# HIGH_CURR_MOS.net
KiCad netlist of a schematic drawn in Altium Designer
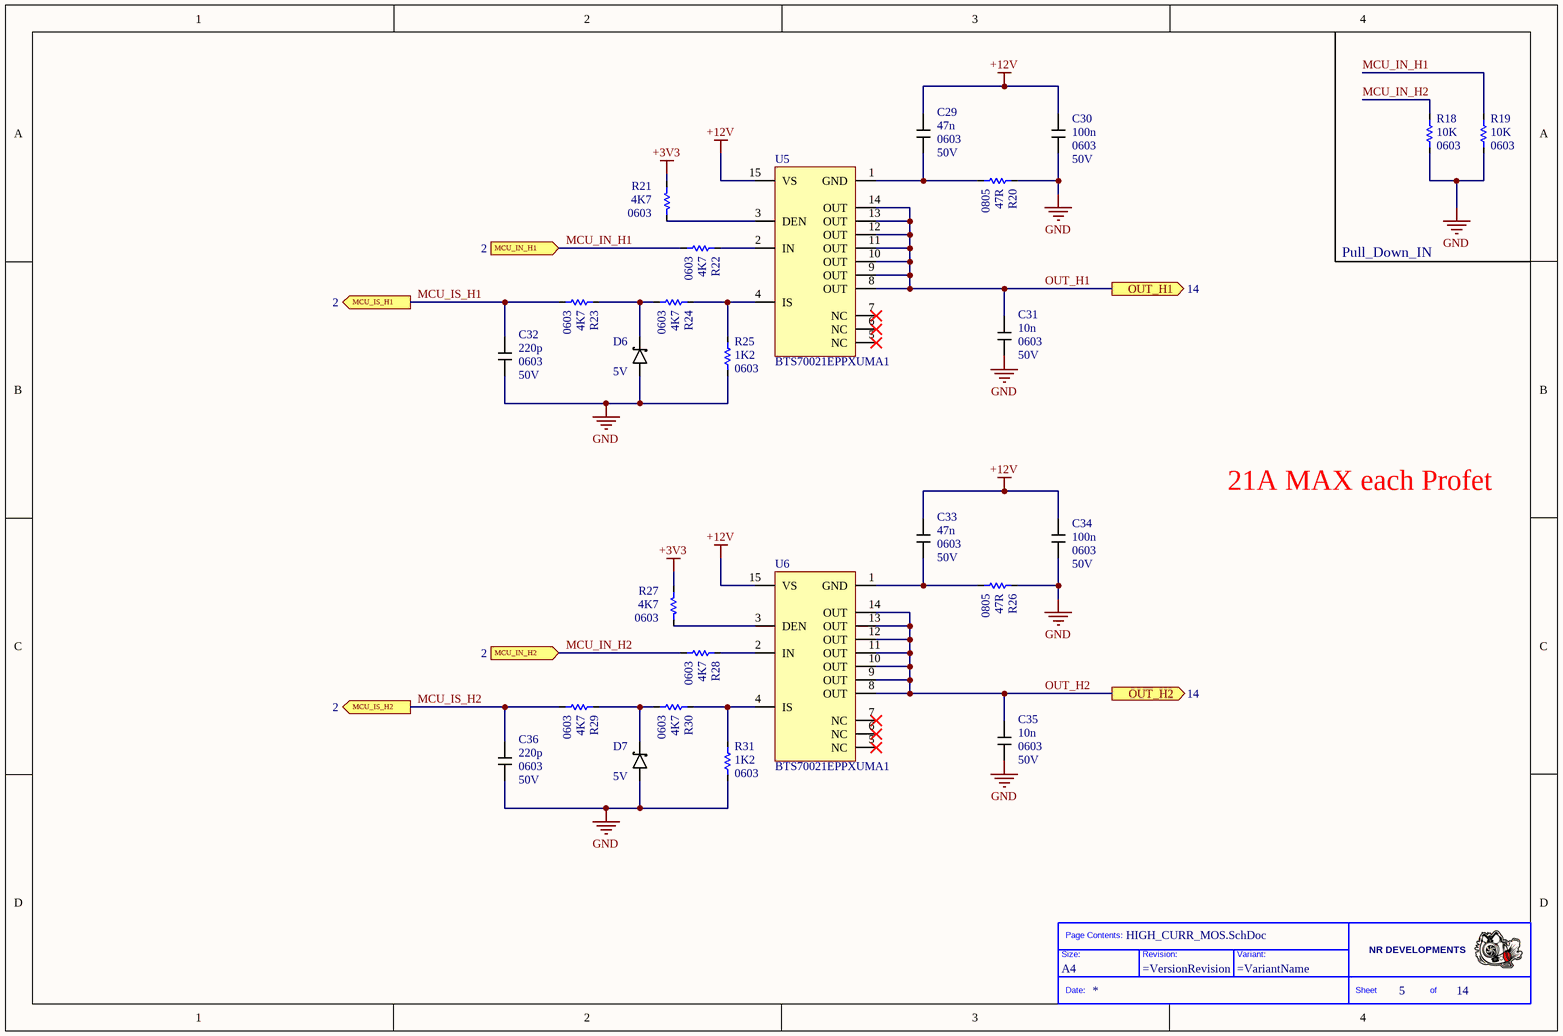
[diagram p0: HIGH_CURR_MOS.SchDoc]

(export (version "E")
  (design (tool "Eeschema 10.0.6"))
  (components
    (comp (ref "C29")
      (value "47n")
      (footprint "CAPC1608X09M")
      (fields
        (field (name "MANUFACTURER") "KEMET")
        (field (name "PARTNUMBER") "C0603C473M5RACTU")
        (field (name "CASE") "0603")
        (field (name "VOLTAGE") "50V")
        (field (name "Comment") "CAP")
      )
      (libsource (lib "My_LIB") (part "CAP"))
    )
    (comp (ref "C30")
      (value "100n")
      (footprint "CAPC1608X09M")
      (fields
        (field (name "CASE") "0603")
        (field (name "VOLTAGE") "50V")
        (field (name "MANUFACTURER") "KEMET")
        (field (name "PARTNUMBER") "C0603C104K5RACTU")
        (field (name "Comment") "CAP")
      )
      (libsource (lib "My_LIB") (part "CAP"))
    )
    (comp (ref "C31")
      (value "10n")
      (footprint "CAPC1608X09M")
      (fields
        (field (name "MANUFACTURER") "KEMET")
        (field (name "PARTNUMBER") "C0603C103M5RACTM")
        (field (name "CASE") "0603")
        (field (name "VOLTAGE") "50V")
        (field (name "Comment") "CAP")
      )
      (libsource (lib "My_LIB") (part "CAP"))
    )
    (comp (ref "C32")
      (value "220p")
      (footprint "CAPC1608X09M")
      (fields
        (field (name "MANUFACTURER") "KEMET")
        (field (name "PARTNUMBER") "C0603C221J5RACTU")
        (field (name "CASE") "0603")
        (field (name "VOLTAGE") "50V")
        (field (name "Comment") "CAP")
      )
      (libsource (lib "My_LIB") (part "CAP"))
    )
    (comp (ref "C33")
      (value "47n")
      (footprint "CAPC1608X09M")
      (fields
        (field (name "MANUFACTURER") "KEMET")
        (field (name "PARTNUMBER") "C0603C473M5RACTU")
        (field (name "CASE") "0603")
        (field (name "VOLTAGE") "50V")
        (field (name "Comment") "CAP")
      )
      (libsource (lib "My_LIB") (part "CAP"))
    )
    (comp (ref "C34")
      (value "100n")
      (footprint "CAPC1608X09M")
      (fields
        (field (name "CASE") "0603")
        (field (name "VOLTAGE") "50V")
        (field (name "MANUFACTURER") "KEMET")
        (field (name "PARTNUMBER") "C0603C104K5RACTU")
        (field (name "Comment") "CAP")
      )
      (libsource (lib "My_LIB") (part "CAP"))
    )
    (comp (ref "C35")
      (value "10n")
      (footprint "CAPC1608X09M")
      (fields
        (field (name "MANUFACTURER") "KEMET")
        (field (name "PARTNUMBER") "C0603C103M5RACTM")
        (field (name "CASE") "0603")
        (field (name "VOLTAGE") "50V")
        (field (name "Comment") "CAP")
      )
      (libsource (lib "My_LIB") (part "CAP"))
    )
    (comp (ref "C36")
      (value "220p")
      (footprint "CAPC1608X09M")
      (fields
        (field (name "MANUFACTURER") "KEMET")
        (field (name "PARTNUMBER") "C0603C221J5RACTU")
        (field (name "CASE") "0603")
        (field (name "VOLTAGE") "50V")
        (field (name "Comment") "CAP")
      )
      (libsource (lib "My_LIB") (part "CAP"))
    )
    (comp (ref "D6")
      (value "5V")
      (footprint "SOT65P210X100-3N - AC")
      (fields
        (field (name "MANUFACTURER") "NEXPERIA")
        (field (name "PARTNUMBER") "BZX84W-C4V7-QX")
        (field (name "Comment") "Diode_Schottky")
      )
      (libsource (lib "My_LIB") (part "Diode_Schottky"))
    )
    (comp (ref "D7")
      (value "5V")
      (footprint "SOT65P210X100-3N - AC")
      (fields
        (field (name "MANUFACTURER") "Nexperia")
        (field (name "PARTNUMBER") "BZX84W-C4V7-QX")
        (field (name "Comment") "Diode_Schottky")
      )
      (libsource (lib "My_LIB") (part "Diode_Schottky"))
    )
    (comp (ref "R18")
      (value "10K")
      (footprint "RESC1608X06M")
      (fields
        (field (name "CASE") "0603")
        (field (name "MANUFACTURER") "YAGEO")
        (field (name "PARTNUMBER") "AC0603FR-0710KL")
        (field (name "Comment") "Res")
      )
      (libsource (lib "My_LIB") (part "Resistor"))
    )
    (comp (ref "R19")
      (value "10K")
      (footprint "RESC1608X06M")
      (fields
        (field (name "CASE") "0603")
        (field (name "MANUFACTURER") "YAGEO")
        (field (name "PARTNUMBER") "AC0603FR-0710KL")
        (field (name "Comment") "Res")
      )
      (libsource (lib "My_LIB") (part "Resistor"))
    )
    (comp (ref "R20")
      (value "47R")
      (footprint "RESC2012X06N")
      (fields
        (field (name "MANUFACTURER") "Vishay")
        (field (name "CASE") "0805")
        (field (name "PARTNUMBER") "CRCW080547R0FKEA")
        (field (name "Comment") "Res")
      )
      (libsource (lib "My_LIB") (part "Resistor"))
    )
    (comp (ref "R21")
      (value "4K7")
      (footprint "RESC1608X06M")
      (fields
        (field (name "CASE") "0603")
        (field (name "MANUFACTURER") "YAGEO")
        (field (name "PARTNUMBER") "RC0603FR-074K7L")
        (field (name "Comment") "Res")
      )
      (libsource (lib "My_LIB") (part "Resistor"))
    )
    (comp (ref "R22")
      (value "4K7")
      (footprint "RESC1608X06M")
      (fields
        (field (name "MANUFACTURER") "YAGEO")
        (field (name "CASE") "0603")
        (field (name "PARTNUMBER") "RC0603FR-074K7L")
        (field (name "Comment") "Res")
      )
      (libsource (lib "My_LIB") (part "Resistor"))
    )
    (comp (ref "R23")
      (value "4K7")
      (footprint "RESC1608X06M")
      (fields
        (field (name "MANUFACTURER") "YAGEO")
        (field (name "CASE") "0603")
        (field (name "PARTNUMBER") "RC0603FR-074K7L")
        (field (name "Comment") "Res")
      )
      (libsource (lib "My_LIB") (part "Resistor"))
    )
    (comp (ref "R24")
      (value "4K7")
      (footprint "RESC1608X06M")
      (fields
        (field (name "MANUFACTURER") "YAGEO")
        (field (name "CASE") "0603")
        (field (name "PARTNUMBER") "RC0603FR-074K7L")
        (field (name "Comment") "Res")
      )
      (libsource (lib "My_LIB") (part "Resistor"))
    )
    (comp (ref "R25")
      (value "1K2")
      (footprint "RESC1608X06M")
      (fields
        (field (name "MANUFACTURER") "Vishay")
        (field (name "CASE") "0603")
        (field (name "PARTNUMBER") "CRCW06031K20FKEA")
        (field (name "Comment") "Res")
      )
      (libsource (lib "My_LIB") (part "Resistor"))
    )
    (comp (ref "R26")
      (value "47R")
      (footprint "RESC2012X06N")
      (fields
        (field (name "MANUFACTURER") "Vishay")
        (field (name "CASE") "0805")
        (field (name "PARTNUMBER") "CRCW080547R0FKEA")
        (field (name "Comment") "Res")
      )
      (libsource (lib "My_LIB") (part "Resistor"))
    )
    (comp (ref "R27")
      (value "4K7")
      (footprint "RESC1608X06M")
      (fields
        (field (name "CASE") "0603")
        (field (name "MANUFACTURER") "YAGEO")
        (field (name "PARTNUMBER") "RC0603FR-074K7L")
        (field (name "Comment") "Res")
      )
      (libsource (lib "My_LIB") (part "Resistor"))
    )
    (comp (ref "R28")
      (value "4K7")
      (footprint "RESC1608X06M")
      (fields
        (field (name "MANUFACTURER") "YAGEO")
        (field (name "CASE") "0603")
        (field (name "PARTNUMBER") "RC0603FR-074K7L")
        (field (name "Comment") "Res")
      )
      (libsource (lib "My_LIB") (part "Resistor"))
    )
    (comp (ref "R29")
      (value "4K7")
      (footprint "RESC1608X06M")
      (fields
        (field (name "MANUFACTURER") "YAGEO")
        (field (name "CASE") "0603")
        (field (name "PARTNUMBER") "RC0603FR-074K7L")
        (field (name "Comment") "Res")
      )
      (libsource (lib "My_LIB") (part "Resistor"))
    )
    (comp (ref "R30")
      (value "4K7")
      (footprint "RESC1608X06M")
      (fields
        (field (name "MANUFACTURER") "YAGEO")
        (field (name "CASE") "0603")
        (field (name "PARTNUMBER") "RC0603FR-074K7L")
        (field (name "Comment") "Res")
      )
      (libsource (lib "My_LIB") (part "Resistor"))
    )
    (comp (ref "R31")
      (value "1K2")
      (footprint "RESC1608X06M")
      (fields
        (field (name "MANUFACTURER") "Vishay")
        (field (name "CASE") "0603")
        (field (name "PARTNUMBER") "CRCW06031K20FKEA")
        (field (name "Comment") "Res")
      )
      (libsource (lib "My_LIB") (part "Resistor"))
    )
    (comp (ref "U5")
      (value "BTS70021EPPXUMA1")
      (footprint "SOP65P600X115-15")
      (description "Smart High-Side Power Switch 21A")
      (fields (field (name "MANUFACTURER") "Infineon Technologies") (field (name "Comment") "BTS7002-1EPP"))
      (libsource (lib "My_LIB") (part "BTS7002-1EPP"))
    )
    (comp (ref "U6")
      (value "BTS70021EPPXUMA1")
      (footprint "SOP65P600X115-15")
      (description "Smart High-Side Power Switch 21A")
      (fields (field (name "MANUFACTURER") "Infineon Technologies") (field (name "Comment") "BTS7002-1EPP"))
      (libsource (lib "My_LIB") (part "BTS7002-1EPP"))
    )
  )
  (nets
    (net (code "1") (name "+3V3") (class "Default")
      (node (ref "R21") (pin "2") (pinfunction "2_2") (pintype "passive"))
      (node (ref "R27") (pin "2") (pinfunction "2_2") (pintype "passive"))
    )
    (net (code "2") (name "+12V") (class "Default")
      (node (ref "C29") (pin "1") (pinfunction "1_1") (pintype "passive"))
      (node (ref "C30") (pin "1") (pinfunction "1_1") (pintype "passive"))
      (node (ref "C33") (pin "1") (pinfunction "1_1") (pintype "passive"))
      (node (ref "C34") (pin "1") (pinfunction "1_1") (pintype "passive"))
      (node (ref "U5") (pin "15") (pinfunction "VS_15") (pintype "power_in"))
      (node (ref "U6") (pin "15") (pinfunction "VS_15") (pintype "power_in"))
    )
    (net (code "3") (name "/MCU_IN_H1") (class "Default")
      (node (ref "R19") (pin "2") (pinfunction "2_2") (pintype "passive"))
      (node (ref "R22") (pin "1") (pinfunction "1_1") (pintype "passive"))
    )
    (net (code "4") (name "/MCU_IN_H2") (class "Default")
      (node (ref "R18") (pin "2") (pinfunction "2_2") (pintype "passive"))
      (node (ref "R28") (pin "1") (pinfunction "1_1") (pintype "passive"))
    )
    (net (code "5") (name "/MCU_IS_H1") (class "Default")
      (node (ref "C32") (pin "1") (pinfunction "1_1") (pintype "passive"))
      (node (ref "R23") (pin "1") (pinfunction "1_1") (pintype "passive"))
    )
    (net (code "6") (name "/MCU_IS_H2") (class "Default")
      (node (ref "C36") (pin "1") (pinfunction "1_1") (pintype "passive"))
      (node (ref "R29") (pin "1") (pinfunction "1_1") (pintype "passive"))
    )
    (net (code "7") (name "/OUT_H1") (class "Default")
      (node (ref "C31") (pin "1") (pinfunction "1_1") (pintype "passive"))
      (node (ref "U5") (pin "10") (pinfunction "OUT_10") (pintype "passive"))
      (node (ref "U5") (pin "11") (pinfunction "OUT_11") (pintype "passive"))
      (node (ref "U5") (pin "12") (pinfunction "OUT_12") (pintype "passive"))
      (node (ref "U5") (pin "13") (pinfunction "OUT_13") (pintype "passive"))
      (node (ref "U5") (pin "14") (pinfunction "OUT_14") (pintype "passive"))
      (node (ref "U5") (pin "8") (pinfunction "OUT_8") (pintype "passive"))
      (node (ref "U5") (pin "9") (pinfunction "OUT_9") (pintype "passive"))
    )
    (net (code "8") (name "/OUT_H2") (class "Default")
      (node (ref "C35") (pin "1") (pinfunction "1_1") (pintype "passive"))
      (node (ref "U6") (pin "10") (pinfunction "OUT_10") (pintype "passive"))
      (node (ref "U6") (pin "11") (pinfunction "OUT_11") (pintype "passive"))
      (node (ref "U6") (pin "12") (pinfunction "OUT_12") (pintype "passive"))
      (node (ref "U6") (pin "13") (pinfunction "OUT_13") (pintype "passive"))
      (node (ref "U6") (pin "14") (pinfunction "OUT_14") (pintype "passive"))
      (node (ref "U6") (pin "8") (pinfunction "OUT_8") (pintype "passive"))
      (node (ref "U6") (pin "9") (pinfunction "OUT_9") (pintype "passive"))
    )
    (net (code "9") (name "GND") (class "Default")
      (node (ref "C30") (pin "2") (pinfunction "2_2") (pintype "passive"))
      (node (ref "C31") (pin "2") (pinfunction "2_2") (pintype "passive"))
      (node (ref "C32") (pin "2") (pinfunction "2_2") (pintype "passive"))
      (node (ref "C34") (pin "2") (pinfunction "2_2") (pintype "passive"))
      (node (ref "C35") (pin "2") (pinfunction "2_2") (pintype "passive"))
      (node (ref "C36") (pin "2") (pinfunction "2_2") (pintype "passive"))
      (node (ref "D6") (pin "A") (pinfunction "A_A") (pintype "passive"))
      (node (ref "D7") (pin "A") (pinfunction "A_A") (pintype "passive"))
      (node (ref "R18") (pin "1") (pinfunction "1_1") (pintype "passive"))
      (node (ref "R19") (pin "1") (pinfunction "1_1") (pintype "passive"))
      (node (ref "R20") (pin "2") (pinfunction "2_2") (pintype "passive"))
      (node (ref "R25") (pin "1") (pinfunction "1_1") (pintype "passive"))
      (node (ref "R26") (pin "2") (pinfunction "2_2") (pintype "passive"))
      (node (ref "R31") (pin "1") (pinfunction "1_1") (pintype "passive"))
    )
    (net (code "10") (name "Net-(D6-PadC)") (class "Default")
      (node (ref "D6") (pin "C") (pinfunction "C_C") (pintype "passive"))
      (node (ref "R23") (pin "2") (pinfunction "2_2") (pintype "passive"))
      (node (ref "R24") (pin "1") (pinfunction "1_1") (pintype "passive"))
    )
    (net (code "11") (name "Net-(D7-PadC)") (class "Default")
      (node (ref "D7") (pin "C") (pinfunction "C_C") (pintype "passive"))
      (node (ref "R29") (pin "2") (pinfunction "2_2") (pintype "passive"))
      (node (ref "R30") (pin "1") (pinfunction "1_1") (pintype "passive"))
    )
    (net (code "12") (name "Net-(U5-DEN)") (class "Default")
      (node (ref "R21") (pin "1") (pinfunction "1_1") (pintype "passive"))
      (node (ref "U5") (pin "3") (pinfunction "DEN_3") (pintype "passive"))
    )
    (net (code "13") (name "Net-(U5-GND)") (class "Default")
      (node (ref "C29") (pin "2") (pinfunction "2_2") (pintype "passive"))
      (node (ref "R20") (pin "1") (pinfunction "1_1") (pintype "passive"))
      (node (ref "U5") (pin "1") (pinfunction "GND_1") (pintype "power_in"))
    )
    (net (code "14") (name "Net-(U5-IN)") (class "Default")
      (node (ref "R22") (pin "2") (pinfunction "2_2") (pintype "passive"))
      (node (ref "U5") (pin "2") (pinfunction "IN_2") (pintype "passive"))
    )
    (net (code "15") (name "Net-(U5-IS)") (class "Default")
      (node (ref "R24") (pin "2") (pinfunction "2_2") (pintype "passive"))
      (node (ref "R25") (pin "2") (pinfunction "2_2") (pintype "passive"))
      (node (ref "U5") (pin "4") (pinfunction "IS_4") (pintype "passive"))
    )
    (net (code "16") (name "Net-(U6-DEN)") (class "Default")
      (node (ref "R27") (pin "1") (pinfunction "1_1") (pintype "passive"))
      (node (ref "U6") (pin "3") (pinfunction "DEN_3") (pintype "passive"))
    )
    (net (code "17") (name "Net-(U6-GND)") (class "Default")
      (node (ref "C33") (pin "2") (pinfunction "2_2") (pintype "passive"))
      (node (ref "R26") (pin "1") (pinfunction "1_1") (pintype "passive"))
      (node (ref "U6") (pin "1") (pinfunction "GND_1") (pintype "power_in"))
    )
    (net (code "18") (name "Net-(U6-IN)") (class "Default")
      (node (ref "R28") (pin "2") (pinfunction "2_2") (pintype "passive"))
      (node (ref "U6") (pin "2") (pinfunction "IN_2") (pintype "passive"))
    )
    (net (code "19") (name "Net-(U6-IS)") (class "Default")
      (node (ref "R30") (pin "2") (pinfunction "2_2") (pintype "passive"))
      (node (ref "R31") (pin "2") (pinfunction "2_2") (pintype "passive"))
      (node (ref "U6") (pin "4") (pinfunction "IS_4") (pintype "passive"))
    )
    (net (code "20") (name "unconnected-(U5-NC-Pad5)") (class "Default")
      (node (ref "U5") (pin "5") (pinfunction "NC_5") (pintype "passive+no_connect"))
    )
    (net (code "21") (name "unconnected-(U5-NC-Pad6)") (class "Default")
      (node (ref "U5") (pin "6") (pinfunction "NC_6") (pintype "passive+no_connect"))
    )
    (net (code "22") (name "unconnected-(U5-NC-Pad7)") (class "Default")
      (node (ref "U5") (pin "7") (pinfunction "NC_7") (pintype "passive+no_connect"))
    )
    (net (code "23") (name "unconnected-(U6-NC-Pad5)") (class "Default")
      (node (ref "U6") (pin "5") (pinfunction "NC_5") (pintype "passive+no_connect"))
    )
    (net (code "24") (name "unconnected-(U6-NC-Pad6)") (class "Default")
      (node (ref "U6") (pin "6") (pinfunction "NC_6") (pintype "passive+no_connect"))
    )
    (net (code "25") (name "unconnected-(U6-NC-Pad7)") (class "Default")
      (node (ref "U6") (pin "7") (pinfunction "NC_7") (pintype "passive+no_connect"))
    )
  )
)
